# Caprica_Charger.net
KiCad netlist of a schematic drawn in EAGLE
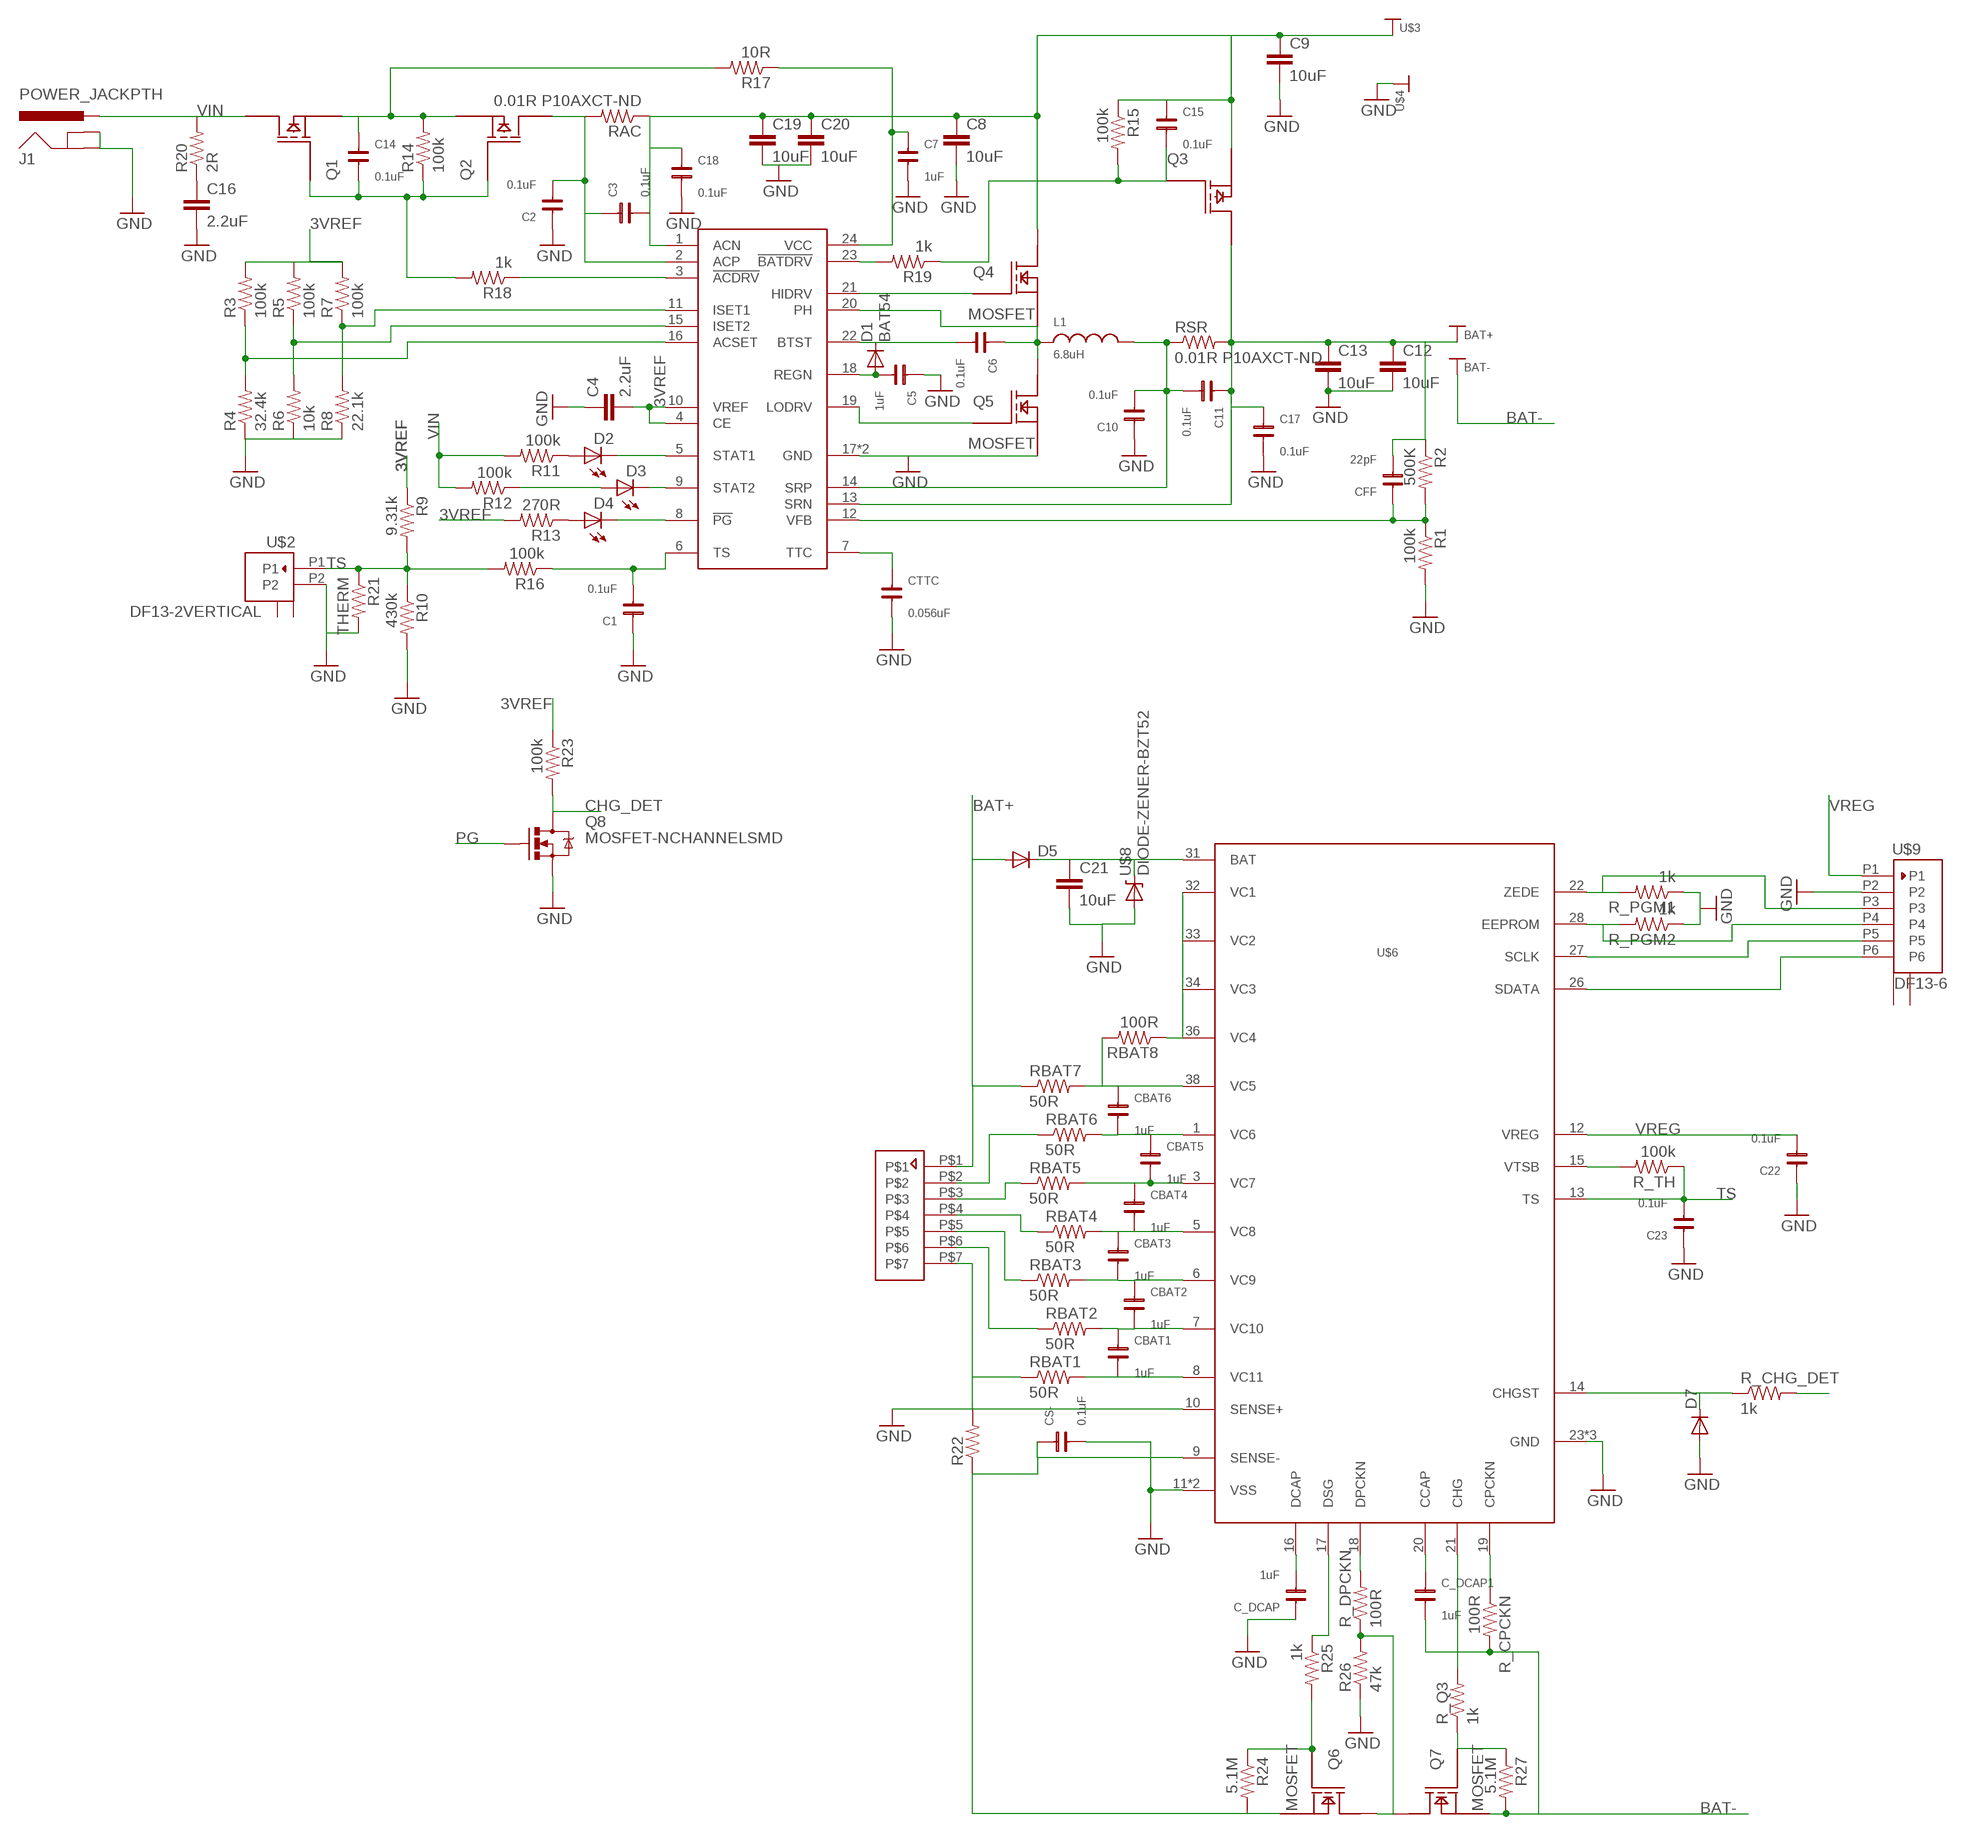
[diagram p0: schematic, sheet 1]

(export (version "E")
  (design (tool "Eeschema 10.0.6"))
  (components
    (comp (ref "BAT+")
      (value "HIGHCURRENTPAD2")
      (footprint "eagle-import:HIGH_CURRENT_PAD2")
      (libsource (lib "eagle-import") (part "HIGHCURRENTPAD2"))
    )
    (comp (ref "BAT-")
      (value "HIGHCURRENTPAD2")
      (footprint "eagle-import:HIGH_CURRENT_PAD2")
      (libsource (lib "eagle-import") (part "HIGHCURRENTPAD2"))
    )
    (comp (ref "C1")
      (value "0.1uF")
      (footprint "eagle-import:0603-CAP")
      (libsource (lib "eagle-import") (part "CAPACITOR0603-CAP"))
    )
    (comp (ref "C2")
      (value "0.1uF")
      (footprint "eagle-import:0603-CAP")
      (libsource (lib "eagle-import") (part "CAPACITOR0603-CAP"))
    )
    (comp (ref "C3")
      (value "0.1uF")
      (footprint "eagle-import:0603-CAP")
      (libsource (lib "eagle-import") (part "CAPACITOR0603-CAP"))
    )
    (comp (ref "C4")
      (value "2.2uF")
      (footprint "eagle-import:1206")
      (libsource (lib "eagle-import") (part "CAP1206"))
    )
    (comp (ref "C5")
      (value "1uF")
      (footprint "eagle-import:0603-CAP")
      (libsource (lib "eagle-import") (part "CAPACITOR0603-CAP"))
    )
    (comp (ref "C6")
      (value "0.1uF")
      (footprint "eagle-import:0603-CAP")
      (libsource (lib "eagle-import") (part "CAPACITOR0603-CAP"))
    )
    (comp (ref "C7")
      (value "1uF")
      (footprint "eagle-import:0603-CAP")
      (libsource (lib "eagle-import") (part "CAPACITOR0603-CAP"))
    )
    (comp (ref "C8")
      (value "10uF")
      (footprint "eagle-import:1206")
      (libsource (lib "eagle-import") (part "CAP1206"))
    )
    (comp (ref "C9")
      (value "10uF")
      (footprint "eagle-import:1206")
      (libsource (lib "eagle-import") (part "CAP1206"))
    )
    (comp (ref "C10")
      (value "0.1uF")
      (footprint "eagle-import:0603-CAP")
      (libsource (lib "eagle-import") (part "CAPACITOR0603-CAP"))
    )
    (comp (ref "C11")
      (value "0.1uF")
      (footprint "eagle-import:0603-CAP")
      (libsource (lib "eagle-import") (part "CAPACITOR0603-CAP"))
    )
    (comp (ref "C12")
      (value "10uF")
      (footprint "eagle-import:1206")
      (libsource (lib "eagle-import") (part "CAP1206"))
    )
    (comp (ref "C13")
      (value "10uF")
      (footprint "eagle-import:1206")
      (libsource (lib "eagle-import") (part "CAP1206"))
    )
    (comp (ref "C14")
      (value "0.1uF")
      (footprint "eagle-import:0603-CAP")
      (libsource (lib "eagle-import") (part "CAPACITOR0603-CAP"))
    )
    (comp (ref "C15")
      (value "0.1uF")
      (footprint "eagle-import:0603-CAP")
      (libsource (lib "eagle-import") (part "CAPACITOR0603-CAP"))
    )
    (comp (ref "C16")
      (value "2.2uF")
      (footprint "eagle-import:1206")
      (libsource (lib "eagle-import") (part "CAP1206"))
    )
    (comp (ref "C17")
      (value "0.1uF")
      (footprint "eagle-import:0603-CAP")
      (libsource (lib "eagle-import") (part "CAPACITOR0603-CAP"))
    )
    (comp (ref "C18")
      (value "0.1uF")
      (footprint "eagle-import:0603-CAP")
      (libsource (lib "eagle-import") (part "CAPACITOR0603-CAP"))
    )
    (comp (ref "C19")
      (value "10uF")
      (footprint "eagle-import:1206")
      (libsource (lib "eagle-import") (part "CAP1206"))
    )
    (comp (ref "C20")
      (value "10uF")
      (footprint "eagle-import:1206")
      (libsource (lib "eagle-import") (part "CAP1206"))
    )
    (comp (ref "C21")
      (value "10uF")
      (footprint "eagle-import:1206")
      (libsource (lib "eagle-import") (part "CAP1206"))
    )
    (comp (ref "C22")
      (value "0.1uF")
      (footprint "eagle-import:0603-CAP")
      (libsource (lib "eagle-import") (part "CAPACITOR0603-CAP"))
    )
    (comp (ref "C23")
      (value "0.1uF")
      (footprint "eagle-import:0603-CAP")
      (libsource (lib "eagle-import") (part "CAPACITOR0603-CAP"))
    )
    (comp (ref "CBAT1")
      (value "1uF")
      (footprint "eagle-import:0603-CAP")
      (libsource (lib "eagle-import") (part "CAPACITOR0603-CAP"))
    )
    (comp (ref "CBAT2")
      (value "1uF")
      (footprint "eagle-import:0603-CAP")
      (libsource (lib "eagle-import") (part "CAPACITOR0603-CAP"))
    )
    (comp (ref "CBAT3")
      (value "1uF")
      (footprint "eagle-import:0603-CAP")
      (libsource (lib "eagle-import") (part "CAPACITOR0603-CAP"))
    )
    (comp (ref "CBAT4")
      (value "1uF")
      (footprint "eagle-import:0603-CAP")
      (libsource (lib "eagle-import") (part "CAPACITOR0603-CAP"))
    )
    (comp (ref "CBAT5")
      (value "1uF")
      (footprint "eagle-import:0603-CAP")
      (libsource (lib "eagle-import") (part "CAPACITOR0603-CAP"))
    )
    (comp (ref "CBAT6")
      (value "1uF")
      (footprint "eagle-import:0603-CAP")
      (libsource (lib "eagle-import") (part "CAPACITOR0603-CAP"))
    )
    (comp (ref "CFF")
      (value "22pF")
      (footprint "eagle-import:0603-CAP")
      (libsource (lib "eagle-import") (part "CAPACITOR0603-CAP"))
    )
    (comp (ref "CS-")
      (value "0.1uF")
      (footprint "eagle-import:0603-CAP")
      (libsource (lib "eagle-import") (part "CAPACITOR0603-CAP"))
    )
    (comp (ref "CTTC")
      (value "0.056uF")
      (footprint "eagle-import:0603-CAP")
      (libsource (lib "eagle-import") (part "CAPACITOR0603-CAP"))
    )
    (comp (ref "C_DCAP")
      (value "1uF")
      (footprint "eagle-import:0603-CAP")
      (libsource (lib "eagle-import") (part "CAPACITOR0603-CAP"))
    )
    (comp (ref "C_DCAP1")
      (value "1uF")
      (footprint "eagle-import:0603-CAP")
      (libsource (lib "eagle-import") (part "CAPACITOR0603-CAP"))
    )
    (comp (ref "D1")
      (value "BAT54")
      (footprint "eagle-import:SOT23-3")
      (libsource (lib "eagle-import") (part "DIODESOT23"))
    )
    (comp (ref "D2")
      (value "LED1206")
      (footprint "eagle-import:LED-1206")
      (libsource (lib "eagle-import") (part "LED1206"))
    )
    (comp (ref "D3")
      (value "LED1206")
      (footprint "eagle-import:LED-1206")
      (libsource (lib "eagle-import") (part "LED1206"))
    )
    (comp (ref "D4")
      (value "LED1206")
      (footprint "eagle-import:LED-1206")
      (libsource (lib "eagle-import") (part "LED1206"))
    )
    (comp (ref "D5")
      (value "DIODESMA")
      (footprint "eagle-import:SMA-DIODE")
      (libsource (lib "eagle-import") (part "DIODESMA"))
    )
    (comp (ref "D7")
      (value "DIODESOD")
      (footprint "eagle-import:SOD-323")
      (libsource (lib "eagle-import") (part "DIODESOD"))
    )
    (comp (ref "J1")
      (value "POWER_JACKPTH")
      (footprint "eagle-import:POWER_JACK_PTH")
      (libsource (lib "eagle-import") (part "POWER_JACKPTH"))
    )
    (comp (ref "L1")
      (value "6.8uH")
      (footprint "eagle-import:SDR0403_INDUCTOR")
      (libsource (lib "eagle-import") (part "INDUCTORSDR0403"))
    )
    (comp (ref "Q1")
      (value "MOSFET_PCH")
      (footprint "eagle-import:POWERPAK_1212-8")
      (libsource (lib "eagle-import") (part "MOSFET_PCH"))
    )
    (comp (ref "Q2")
      (value "MOSFET_PCH")
      (footprint "eagle-import:POWERPAK_1212-8")
      (libsource (lib "eagle-import") (part "MOSFET_PCH"))
    )
    (comp (ref "Q3")
      (value "MOSFET_PCH")
      (footprint "eagle-import:POWERPAK_1212-8")
      (libsource (lib "eagle-import") (part "MOSFET_PCH"))
    )
    (comp (ref "Q4")
      (value "MOSFET")
      (footprint "eagle-import:POWERPAK_1212-8")
      (libsource (lib "eagle-import") (part "MOSFET"))
    )
    (comp (ref "Q5")
      (value "MOSFET")
      (footprint "eagle-import:POWERPAK_1212-8")
      (libsource (lib "eagle-import") (part "MOSFET"))
    )
    (comp (ref "Q6")
      (value "MOSFET")
      (footprint "eagle-import:POWERPAK_1212-8")
      (libsource (lib "eagle-import") (part "MOSFET"))
    )
    (comp (ref "Q7")
      (value "MOSFET")
      (footprint "eagle-import:POWERPAK_1212-8")
      (libsource (lib "eagle-import") (part "MOSFET"))
    )
    (comp (ref "Q8")
      (value "MOSFET-NCHANNELSMD")
      (footprint "eagle-import:SOT23-3")
      (libsource (lib "eagle-import") (part "MOSFET-NCHANNELSMD"))
    )
    (comp (ref "R1")
      (value "100k")
      (footprint "eagle-import:0603-RES")
      (libsource (lib "eagle-import") (part "RESISTOR"))
    )
    (comp (ref "R2")
      (value "500K")
      (footprint "eagle-import:0603-RES")
      (libsource (lib "eagle-import") (part "RESISTOR"))
    )
    (comp (ref "R3")
      (value "100k")
      (footprint "eagle-import:0603-RES")
      (libsource (lib "eagle-import") (part "RESISTOR"))
    )
    (comp (ref "R4")
      (value "32.4k")
      (footprint "eagle-import:0603-RES")
      (libsource (lib "eagle-import") (part "RESISTOR"))
    )
    (comp (ref "R5")
      (value "100k")
      (footprint "eagle-import:0603-RES")
      (libsource (lib "eagle-import") (part "RESISTOR"))
    )
    (comp (ref "R6")
      (value "10k")
      (footprint "eagle-import:0603-RES")
      (libsource (lib "eagle-import") (part "RESISTOR"))
    )
    (comp (ref "R7")
      (value "100k")
      (footprint "eagle-import:0603-RES")
      (libsource (lib "eagle-import") (part "RESISTOR"))
    )
    (comp (ref "R8")
      (value "22.1k")
      (footprint "eagle-import:0603-RES")
      (libsource (lib "eagle-import") (part "RESISTOR"))
    )
    (comp (ref "R9")
      (value "9.31k")
      (footprint "eagle-import:0603-RES")
      (libsource (lib "eagle-import") (part "RESISTOR"))
    )
    (comp (ref "R10")
      (value "430k")
      (footprint "eagle-import:0603-RES")
      (libsource (lib "eagle-import") (part "RESISTOR"))
    )
    (comp (ref "R11")
      (value "100k")
      (footprint "eagle-import:0603-RES")
      (libsource (lib "eagle-import") (part "RESISTOR"))
    )
    (comp (ref "R12")
      (value "100k")
      (footprint "eagle-import:0603-RES")
      (libsource (lib "eagle-import") (part "RESISTOR"))
    )
    (comp (ref "R13")
      (value "270R")
      (footprint "eagle-import:0603-RES")
      (libsource (lib "eagle-import") (part "RESISTOR"))
    )
    (comp (ref "R14")
      (value "100k")
      (footprint "eagle-import:0603-RES")
      (libsource (lib "eagle-import") (part "RESISTOR"))
    )
    (comp (ref "R15")
      (value "100k")
      (footprint "eagle-import:0603-RES")
      (libsource (lib "eagle-import") (part "RESISTOR"))
    )
    (comp (ref "R16")
      (value "100k")
      (footprint "eagle-import:0603-RES")
      (libsource (lib "eagle-import") (part "RESISTOR"))
    )
    (comp (ref "R17")
      (value "10R")
      (footprint "eagle-import:0603-RES")
      (libsource (lib "eagle-import") (part "RESISTOR"))
    )
    (comp (ref "R18")
      (value "1k")
      (footprint "eagle-import:0603-RES")
      (libsource (lib "eagle-import") (part "RESISTOR"))
    )
    (comp (ref "R19")
      (value "1k")
      (footprint "eagle-import:0603-RES")
      (libsource (lib "eagle-import") (part "RESISTOR"))
    )
    (comp (ref "R20")
      (value "2R")
      (footprint "eagle-import:0603-RES")
      (libsource (lib "eagle-import") (part "RESISTOR"))
    )
    (comp (ref "R21")
      (value "THERM")
      (footprint "eagle-import:0603-RES")
      (libsource (lib "eagle-import") (part "RESISTOR"))
    )
    (comp (ref "R22")
      (value "RESISTOROHMITE")
      (footprint "eagle-import:OHMITE_FCSL64_CURRENT_SENSE_RESISTOR")
      (libsource (lib "eagle-import") (part "RESISTOROHMITE"))
    )
    (comp (ref "R23")
      (value "100k")
      (footprint "eagle-import:0603-RES")
      (libsource (lib "eagle-import") (part "RESISTOR"))
    )
    (comp (ref "R24")
      (value "5.1M")
      (footprint "eagle-import:0603-RES")
      (libsource (lib "eagle-import") (part "RESISTOR"))
    )
    (comp (ref "R25")
      (value "1k")
      (footprint "eagle-import:0603-RES")
      (libsource (lib "eagle-import") (part "RESISTOR"))
    )
    (comp (ref "R26")
      (value "47k")
      (footprint "eagle-import:0603-RES")
      (libsource (lib "eagle-import") (part "RESISTOR"))
    )
    (comp (ref "R27")
      (value "5.1M")
      (footprint "eagle-import:0603-RES")
      (libsource (lib "eagle-import") (part "RESISTOR"))
    )
    (comp (ref "RAC")
      (value "0.01R P10AXCT-ND")
      (footprint "eagle-import:0603-RES")
      (libsource (lib "eagle-import") (part "RESISTOR"))
    )
    (comp (ref "RBAT1")
      (value "50R")
      (footprint "eagle-import:0603-RES")
      (libsource (lib "eagle-import") (part "RESISTOR"))
    )
    (comp (ref "RBAT2")
      (value "50R")
      (footprint "eagle-import:0603-RES")
      (libsource (lib "eagle-import") (part "RESISTOR"))
    )
    (comp (ref "RBAT3")
      (value "50R")
      (footprint "eagle-import:0603-RES")
      (libsource (lib "eagle-import") (part "RESISTOR"))
    )
    (comp (ref "RBAT4")
      (value "50R")
      (footprint "eagle-import:0603-RES")
      (libsource (lib "eagle-import") (part "RESISTOR"))
    )
    (comp (ref "RBAT5")
      (value "50R")
      (footprint "eagle-import:0603-RES")
      (libsource (lib "eagle-import") (part "RESISTOR"))
    )
    (comp (ref "RBAT6")
      (value "50R")
      (footprint "eagle-import:0603-RES")
      (libsource (lib "eagle-import") (part "RESISTOR"))
    )
    (comp (ref "RBAT7")
      (value "50R")
      (footprint "eagle-import:0603-RES")
      (libsource (lib "eagle-import") (part "RESISTOR"))
    )
    (comp (ref "RBAT8")
      (value "100R")
      (footprint "eagle-import:0603-RES")
      (libsource (lib "eagle-import") (part "RESISTOR"))
    )
    (comp (ref "RSR")
      (value "0.01R P10AXCT-ND")
      (footprint "eagle-import:0603-RES")
      (libsource (lib "eagle-import") (part "RESISTOR"))
    )
    (comp (ref "R_CHG_DET")
      (value "1k")
      (footprint "eagle-import:0603-RES")
      (libsource (lib "eagle-import") (part "RESISTOR"))
    )
    (comp (ref "R_CPCKN")
      (value "100R")
      (footprint "eagle-import:0603-RES")
      (libsource (lib "eagle-import") (part "RESISTOR"))
    )
    (comp (ref "R_DPCKN")
      (value "100R")
      (footprint "eagle-import:0603-RES")
      (libsource (lib "eagle-import") (part "RESISTOR"))
    )
    (comp (ref "R_PGM1")
      (value "1k")
      (footprint "eagle-import:0603-RES")
      (libsource (lib "eagle-import") (part "RESISTOR"))
    )
    (comp (ref "R_PGM2")
      (value "1k")
      (footprint "eagle-import:0603-RES")
      (libsource (lib "eagle-import") (part "RESISTOR"))
    )
    (comp (ref "R_Q3")
      (value "1k")
      (footprint "eagle-import:0603-RES")
      (libsource (lib "eagle-import") (part "RESISTOR"))
    )
    (comp (ref "R_TH")
      (value "100k")
      (footprint "eagle-import:0603-RES")
      (libsource (lib "eagle-import") (part "RESISTOR"))
    )
    (comp (ref "U$1")
      (value "BQ24610_LIPO_CHARGER")
      (footprint "eagle-import:QFN-24_ALT2")
      (libsource (lib "eagle-import") (part "BQ24610_LIPO_CHARGER"))
    )
    (comp (ref "U$2")
      (value "DF13-2VERTICAL")
      (footprint "eagle-import:DF13-2-VERT")
      (libsource (lib "eagle-import") (part "DF13-2VERTICAL"))
    )
    (comp (ref "U$3")
      (value "HIGHCURRENTPAD2")
      (footprint "eagle-import:HIGH_CURRENT_PAD2")
      (libsource (lib "eagle-import") (part "HIGHCURRENTPAD2"))
    )
    (comp (ref "U$4")
      (value "HIGHCURRENTPAD2")
      (footprint "eagle-import:HIGH_CURRENT_PAD2")
      (libsource (lib "eagle-import") (part "HIGHCURRENTPAD2"))
    )
    (comp (ref "U$6")
      (value "BQ77910A_BATTERY_PROTECTOR")
      (footprint "eagle-import:TSSOP38")
      (libsource (lib "eagle-import") (part "BQ77910A_BATTERY_PROTECTOR"))
    )
    (comp (ref "U$7")
      (value "JST_XH_7")
      (footprint "eagle-import:B7B-XH")
      (libsource (lib "eagle-import") (part "JST_XH_7"))
    )
    (comp (ref "U$8")
      (value "DIODE-ZENER-BZT52")
      (footprint "eagle-import:SOD-323")
      (libsource (lib "eagle-import") (part "DIODE-ZENER-BZT52"))
    )
    (comp (ref "U$9")
      (value "DF13-6")
      (footprint "eagle-import:DF13-6-VERT")
      (libsource (lib "eagle-import") (part "DF13-6"))
    )
  )
  (nets
    (net (code "1") (name "/3VREF") (class "Default")
      (node (ref "C4") (pin "2") (pinfunction "2_2") (pintype "passive"))
      (node (ref "R13") (pin "2") (pinfunction "2_2") (pintype "passive"))
      (node (ref "R23") (pin "1") (pinfunction "1_1") (pintype "passive"))
      (node (ref "R3") (pin "2") (pinfunction "2_2") (pintype "passive"))
      (node (ref "R5") (pin "2") (pinfunction "2_2") (pintype "passive"))
      (node (ref "R7") (pin "2") (pinfunction "2_2") (pintype "passive"))
      (node (ref "R9") (pin "1") (pinfunction "1_1") (pintype "passive"))
      (node (ref "U$1") (pin "10") (pinfunction "VREF_10") (pintype "bidirectional"))
      (node (ref "U$1") (pin "4") (pinfunction "CE_4") (pintype "bidirectional"))
    )
    (net (code "2") (name "/BAT+") (class "Default")
      (node (ref "BAT+") (pin "P$1") (pinfunction "P$1_P$1") (pintype "bidirectional"))
      (node (ref "C11") (pin "1") (pinfunction "1_1") (pintype "bidirectional"))
      (node (ref "C12") (pin "1") (pinfunction "1_1") (pintype "passive"))
      (node (ref "C13") (pin "1") (pinfunction "1_1") (pintype "passive"))
      (node (ref "C17") (pin "1") (pinfunction "1_1") (pintype "bidirectional"))
      (node (ref "CFF") (pin "2") (pinfunction "2_2") (pintype "bidirectional"))
      (node (ref "D5") (pin "A") (pinfunction "A_A") (pintype "passive"))
      (node (ref "Q3") (pin "P5") (pinfunction "DRAIN_P5") (pintype "power_in"))
      (node (ref "Q3") (pin "P6") (pinfunction "DRAIN_P6") (pintype "power_in"))
      (node (ref "Q3") (pin "P7") (pinfunction "DRAIN_P7") (pintype "power_in"))
      (node (ref "Q3") (pin "P8") (pinfunction "DRAIN_P8") (pintype "power_in"))
      (node (ref "Q3") (pin "PAD") (pinfunction "DRAIN_PAD") (pintype "power_in"))
      (node (ref "R2") (pin "1") (pinfunction "1_1") (pintype "passive"))
      (node (ref "RBAT7") (pin "1") (pinfunction "1_1") (pintype "passive"))
      (node (ref "RSR") (pin "2") (pinfunction "2_2") (pintype "passive"))
      (node (ref "U$1") (pin "13") (pinfunction "SRN_13") (pintype "bidirectional"))
      (node (ref "U$7") (pin "P$1") (pinfunction "P$1_P$1") (pintype "bidirectional"))
    )
    (net (code "3") (name "/BAT-") (class "Default")
      (node (ref "BAT-") (pin "P$1") (pinfunction "P$1_P$1") (pintype "bidirectional"))
      (node (ref "C_DCAP1") (pin "2") (pinfunction "2_2") (pintype "bidirectional"))
      (node (ref "Q7") (pin "P1") (pinfunction "S_P1") (pintype "bidirectional"))
      (node (ref "Q7") (pin "P2") (pinfunction "S_P2") (pintype "bidirectional"))
      (node (ref "Q7") (pin "P3") (pinfunction "S_P3") (pintype "bidirectional"))
      (node (ref "R27") (pin "2") (pinfunction "2_2") (pintype "passive"))
      (node (ref "R_CPCKN") (pin "2") (pinfunction "2_2") (pintype "passive"))
    )
    (net (code "4") (name "/CHG_DET") (class "Default")
      (node (ref "Q8") (pin "3") (pinfunction "D_3") (pintype "passive"))
      (node (ref "R23") (pin "2") (pinfunction "2_2") (pintype "passive"))
      (node (ref "R_CHG_DET") (pin "2") (pinfunction "2_2") (pintype "passive"))
    )
    (net (code "5") (name "/PG") (class "Default")
      (node (ref "D4") (pin "C") (pinfunction "C_C") (pintype "passive"))
      (node (ref "Q8") (pin "1") (pinfunction "G_1") (pintype "passive"))
      (node (ref "U$1") (pin "8") (pinfunction "~{PG}_8") (pintype "bidirectional"))
    )
    (net (code "6") (name "/TS") (class "Default")
      (node (ref "C23") (pin "2") (pinfunction "2_2") (pintype "bidirectional"))
      (node (ref "R10") (pin "1") (pinfunction "1_1") (pintype "passive"))
      (node (ref "R16") (pin "2") (pinfunction "2_2") (pintype "passive"))
      (node (ref "R21") (pin "1") (pinfunction "1_1") (pintype "passive"))
      (node (ref "R9") (pin "2") (pinfunction "2_2") (pintype "passive"))
      (node (ref "R_TH") (pin "1") (pinfunction "1_1") (pintype "passive"))
      (node (ref "U$2") (pin "P1") (pinfunction "P1_P1") (pintype "bidirectional"))
      (node (ref "U$6") (pin "13") (pinfunction "TS_13") (pintype "bidirectional"))
    )
    (net (code "7") (name "/VIN") (class "Default")
      (node (ref "J1") (pin "PWR") (pinfunction "PWR_PWR") (pintype "bidirectional"))
      (node (ref "Q1") (pin "P5") (pinfunction "DRAIN_P5") (pintype "power_in"))
      (node (ref "Q1") (pin "P6") (pinfunction "DRAIN_P6") (pintype "power_in"))
      (node (ref "Q1") (pin "P7") (pinfunction "DRAIN_P7") (pintype "power_in"))
      (node (ref "Q1") (pin "P8") (pinfunction "DRAIN_P8") (pintype "power_in"))
      (node (ref "Q1") (pin "PAD") (pinfunction "DRAIN_PAD") (pintype "power_in"))
      (node (ref "R11") (pin "2") (pinfunction "2_2") (pintype "passive"))
      (node (ref "R12") (pin "2") (pinfunction "2_2") (pintype "passive"))
      (node (ref "R20") (pin "2") (pinfunction "2_2") (pintype "passive"))
    )
    (net (code "8") (name "/VREG") (class "Default")
      (node (ref "C22") (pin "2") (pinfunction "2_2") (pintype "bidirectional"))
      (node (ref "U$6") (pin "12") (pinfunction "VREG_12") (pintype "bidirectional"))
      (node (ref "U$9") (pin "P1") (pinfunction "P1_P1") (pintype "bidirectional"))
    )
    (net (code "9") (name "GND") (class "Default")
      (node (ref "C1") (pin "1") (pinfunction "1_1") (pintype "bidirectional"))
      (node (ref "C10") (pin "1") (pinfunction "1_1") (pintype "bidirectional"))
      (node (ref "C12") (pin "2") (pinfunction "2_2") (pintype "passive"))
      (node (ref "C13") (pin "2") (pinfunction "2_2") (pintype "passive"))
      (node (ref "C16") (pin "2") (pinfunction "2_2") (pintype "passive"))
      (node (ref "C17") (pin "2") (pinfunction "2_2") (pintype "bidirectional"))
      (node (ref "C18") (pin "2") (pinfunction "2_2") (pintype "bidirectional"))
      (node (ref "C19") (pin "2") (pinfunction "2_2") (pintype "passive"))
      (node (ref "C2") (pin "1") (pinfunction "1_1") (pintype "bidirectional"))
      (node (ref "C20") (pin "2") (pinfunction "2_2") (pintype "passive"))
      (node (ref "C21") (pin "2") (pinfunction "2_2") (pintype "passive"))
      (node (ref "C22") (pin "1") (pinfunction "1_1") (pintype "bidirectional"))
      (node (ref "C23") (pin "1") (pinfunction "1_1") (pintype "bidirectional"))
      (node (ref "C4") (pin "1") (pinfunction "1_1") (pintype "passive"))
      (node (ref "C5") (pin "1") (pinfunction "1_1") (pintype "bidirectional"))
      (node (ref "C7") (pin "2") (pinfunction "2_2") (pintype "bidirectional"))
      (node (ref "C8") (pin "2") (pinfunction "2_2") (pintype "passive"))
      (node (ref "C9") (pin "2") (pinfunction "2_2") (pintype "passive"))
      (node (ref "CS-") (pin "2") (pinfunction "2_2") (pintype "bidirectional"))
      (node (ref "CTTC") (pin "2") (pinfunction "2_2") (pintype "bidirectional"))
      (node (ref "C_DCAP") (pin "1") (pinfunction "1_1") (pintype "bidirectional"))
      (node (ref "D7") (pin "2") (pinfunction "A_2") (pintype "passive"))
      (node (ref "J1") (pin "GND") (pinfunction "GND_GND") (pintype "bidirectional"))
      (node (ref "J1") (pin "GNDBREAK") (pinfunction "GNDBREAK_GNDBREAK") (pintype "bidirectional"))
      (node (ref "Q5") (pin "P1") (pinfunction "S_P1") (pintype "bidirectional"))
      (node (ref "Q5") (pin "P2") (pinfunction "S_P2") (pintype "bidirectional"))
      (node (ref "Q5") (pin "P3") (pinfunction "S_P3") (pintype "bidirectional"))
      (node (ref "Q8") (pin "2") (pinfunction "S_2") (pintype "passive"))
      (node (ref "R1") (pin "2") (pinfunction "2_2") (pintype "passive"))
      (node (ref "R10") (pin "2") (pinfunction "2_2") (pintype "passive"))
      (node (ref "R21") (pin "2") (pinfunction "2_2") (pintype "passive"))
      (node (ref "R22") (pin "P$2") (pinfunction "2_P$2") (pintype "passive"))
      (node (ref "R26") (pin "1") (pinfunction "1_1") (pintype "passive"))
      (node (ref "R4") (pin "1") (pinfunction "1_1") (pintype "passive"))
      (node (ref "R6") (pin "1") (pinfunction "1_1") (pintype "passive"))
      (node (ref "R8") (pin "1") (pinfunction "1_1") (pintype "passive"))
      (node (ref "RBAT1") (pin "1") (pinfunction "1_1") (pintype "passive"))
      (node (ref "R_PGM1") (pin "1") (pinfunction "1_1") (pintype "passive"))
      (node (ref "R_PGM2") (pin "1") (pinfunction "1_1") (pintype "passive"))
      (node (ref "U$1") (pin "17") (pinfunction "GND_17") (pintype "bidirectional"))
      (node (ref "U$1") (pin "EP") (pinfunction "GND_EP") (pintype "bidirectional"))
      (node (ref "U$2") (pin "P2") (pinfunction "P2_P2") (pintype "bidirectional"))
      (node (ref "U$4") (pin "P$1") (pinfunction "P$1_P$1") (pintype "bidirectional"))
      (node (ref "U$6") (pin "10") (pinfunction "SENSE+_10") (pintype "bidirectional"))
      (node (ref "U$6") (pin "11") (pinfunction "VSS_11") (pintype "bidirectional"))
      (node (ref "U$6") (pin "23") (pinfunction "GND_23") (pintype "bidirectional"))
      (node (ref "U$6") (pin "24") (pinfunction "GND_24") (pintype "bidirectional"))
      (node (ref "U$6") (pin "25") (pinfunction "GND_25") (pintype "bidirectional"))
      (node (ref "U$6") (pin "29") (pinfunction "VSS_29") (pintype "bidirectional"))
      (node (ref "U$7") (pin "P$7") (pinfunction "P$7_P$7") (pintype "bidirectional"))
      (node (ref "U$8") (pin "2") (pinfunction "A_2") (pintype "passive"))
      (node (ref "U$9") (pin "P2") (pinfunction "P2_P2") (pintype "bidirectional"))
    )
    (net (code "10") (name "Net-(C14-Pad1)") (class "Default")
      (node (ref "C14") (pin "1") (pinfunction "1_1") (pintype "bidirectional"))
      (node (ref "Q1") (pin "P1") (pinfunction "SOURCE_P1") (pintype "bidirectional"))
      (node (ref "Q1") (pin "P2") (pinfunction "SOURCE_P2") (pintype "bidirectional"))
      (node (ref "Q1") (pin "P3") (pinfunction "SOURCE_P3") (pintype "bidirectional"))
      (node (ref "Q2") (pin "P1") (pinfunction "SOURCE_P1") (pintype "bidirectional"))
      (node (ref "Q2") (pin "P2") (pinfunction "SOURCE_P2") (pintype "bidirectional"))
      (node (ref "Q2") (pin "P3") (pinfunction "SOURCE_P3") (pintype "bidirectional"))
      (node (ref "R14") (pin "2") (pinfunction "2_2") (pintype "passive"))
      (node (ref "R17") (pin "2") (pinfunction "2_2") (pintype "passive"))
    )
    (net (code "11") (name "Net-(C16-Pad1)") (class "Default")
      (node (ref "C16") (pin "1") (pinfunction "1_1") (pintype "passive"))
      (node (ref "R20") (pin "1") (pinfunction "1_1") (pintype "passive"))
    )
    (net (code "12") (name "Net-(D1-A)") (class "Default")
      (node (ref "C5") (pin "2") (pinfunction "2_2") (pintype "bidirectional"))
      (node (ref "D1") (pin "1") (pinfunction "A_1") (pintype "passive"))
      (node (ref "U$1") (pin "18") (pinfunction "REGN_18") (pintype "bidirectional"))
    )
    (net (code "13") (name "Net-(D1-C)") (class "Default")
      (node (ref "C6") (pin "2") (pinfunction "2_2") (pintype "bidirectional"))
      (node (ref "D1") (pin "3") (pinfunction "C_3") (pintype "passive"))
      (node (ref "U$1") (pin "22") (pinfunction "BTST_22") (pintype "bidirectional"))
    )
    (net (code "14") (name "Net-(D2-PadA)") (class "Default")
      (node (ref "D2") (pin "A") (pinfunction "A_A") (pintype "passive"))
      (node (ref "R11") (pin "1") (pinfunction "1_1") (pintype "passive"))
    )
    (net (code "15") (name "Net-(D3-PadA)") (class "Default")
      (node (ref "D3") (pin "A") (pinfunction "A_A") (pintype "passive"))
      (node (ref "R12") (pin "1") (pinfunction "1_1") (pintype "passive"))
    )
    (net (code "16") (name "Net-(D4-PadA)") (class "Default")
      (node (ref "D4") (pin "A") (pinfunction "A_A") (pintype "passive"))
      (node (ref "R13") (pin "1") (pinfunction "1_1") (pintype "passive"))
    )
    (net (code "17") (name "Net-(D7-C)") (class "Default")
      (node (ref "D7") (pin "1") (pinfunction "C_1") (pintype "passive"))
      (node (ref "R_CHG_DET") (pin "1") (pinfunction "1_1") (pintype "passive"))
      (node (ref "U$6") (pin "14") (pinfunction "CHGST_14") (pintype "bidirectional"))
    )
    (net (code "18") (name "Net-(Q1-GATE)") (class "Default")
      (node (ref "C14") (pin "2") (pinfunction "2_2") (pintype "bidirectional"))
      (node (ref "Q1") (pin "P4") (pinfunction "GATE_P4") (pintype "bidirectional"))
      (node (ref "Q2") (pin "P4") (pinfunction "GATE_P4") (pintype "bidirectional"))
      (node (ref "R14") (pin "1") (pinfunction "1_1") (pintype "passive"))
      (node (ref "R18") (pin "2") (pinfunction "2_2") (pintype "passive"))
    )
    (net (code "19") (name "Net-(Q3-GATE)") (class "Default")
      (node (ref "C15") (pin "2") (pinfunction "2_2") (pintype "bidirectional"))
      (node (ref "Q3") (pin "P4") (pinfunction "GATE_P4") (pintype "bidirectional"))
      (node (ref "R15") (pin "2") (pinfunction "2_2") (pintype "passive"))
      (node (ref "R19") (pin "1") (pinfunction "1_1") (pintype "passive"))
    )
    (net (code "20") (name "Net-(Q4-G)") (class "Default")
      (node (ref "Q4") (pin "P4") (pinfunction "G_P4") (pintype "bidirectional"))
      (node (ref "U$1") (pin "21") (pinfunction "HIDRV_21") (pintype "bidirectional"))
    )
    (net (code "21") (name "Net-(Q5-G)") (class "Default")
      (node (ref "Q5") (pin "P4") (pinfunction "G_P4") (pintype "bidirectional"))
      (node (ref "U$1") (pin "19") (pinfunction "LODRV_19") (pintype "bidirectional"))
    )
    (net (code "22") (name "Net-(Q6-D-PadP5)") (class "Default")
      (node (ref "Q6") (pin "P5") (pinfunction "D_P5") (pintype "bidirectional"))
      (node (ref "Q6") (pin "P6") (pinfunction "D_P6") (pintype "bidirectional"))
      (node (ref "Q6") (pin "P7") (pinfunction "D_P7") (pintype "bidirectional"))
      (node (ref "Q6") (pin "P8") (pinfunction "D_P8") (pintype "bidirectional"))
      (node (ref "Q6") (pin "PAD") (pinfunction "D_PAD") (pintype "bidirectional"))
      (node (ref "Q7") (pin "P5") (pinfunction "D_P5") (pintype "bidirectional"))
      (node (ref "Q7") (pin "P6") (pinfunction "D_P6") (pintype "bidirectional"))
      (node (ref "Q7") (pin "P7") (pinfunction "D_P7") (pintype "bidirectional"))
      (node (ref "Q7") (pin "P8") (pinfunction "D_P8") (pintype "bidirectional"))
      (node (ref "Q7") (pin "PAD") (pinfunction "D_PAD") (pintype "bidirectional"))
      (node (ref "R26") (pin "2") (pinfunction "2_2") (pintype "passive"))
      (node (ref "R_DPCKN") (pin "1") (pinfunction "1_1") (pintype "passive"))
    )
    (net (code "23") (name "Net-(Q6-G)") (class "Default")
      (node (ref "Q6") (pin "P4") (pinfunction "G_P4") (pintype "bidirectional"))
      (node (ref "R24") (pin "1") (pinfunction "1_1") (pintype "passive"))
      (node (ref "R25") (pin "2") (pinfunction "2_2") (pintype "passive"))
    )
    (net (code "24") (name "Net-(Q7-G)") (class "Default")
      (node (ref "Q7") (pin "P4") (pinfunction "G_P4") (pintype "bidirectional"))
      (node (ref "R27") (pin "1") (pinfunction "1_1") (pintype "passive"))
      (node (ref "R_Q3") (pin "1") (pinfunction "1_1") (pintype "passive"))
    )
    (net (code "25") (name "Net-(R22-1)") (class "Default")
      (node (ref "CS-") (pin "1") (pinfunction "1_1") (pintype "bidirectional"))
      (node (ref "Q6") (pin "P1") (pinfunction "S_P1") (pintype "bidirectional"))
      (node (ref "Q6") (pin "P2") (pinfunction "S_P2") (pintype "bidirectional"))
      (node (ref "Q6") (pin "P3") (pinfunction "S_P3") (pintype "bidirectional"))
      (node (ref "R22") (pin "P$1") (pinfunction "1_P$1") (pintype "passive"))
      (node (ref "R24") (pin "2") (pinfunction "2_2") (pintype "passive"))
      (node (ref "U$6") (pin "9") (pinfunction "SENSE-_9") (pintype "bidirectional"))
    )
    (net (code "26") (name "Net-(RBAT2-Pad1)") (class "Default")
      (node (ref "RBAT2") (pin "1") (pinfunction "1_1") (pintype "passive"))
      (node (ref "U$7") (pin "P$6") (pinfunction "P$6_P$6") (pintype "bidirectional"))
    )
    (net (code "27") (name "Net-(RBAT3-Pad1)") (class "Default")
      (node (ref "RBAT3") (pin "1") (pinfunction "1_1") (pintype "passive"))
      (node (ref "U$7") (pin "P$5") (pinfunction "P$5_P$5") (pintype "bidirectional"))
    )
    (net (code "28") (name "Net-(RBAT4-Pad1)") (class "Default")
      (node (ref "RBAT4") (pin "1") (pinfunction "1_1") (pintype "passive"))
      (node (ref "U$7") (pin "P$4") (pinfunction "P$4_P$4") (pintype "bidirectional"))
    )
    (net (code "29") (name "Net-(RBAT5-Pad1)") (class "Default")
      (node (ref "RBAT5") (pin "1") (pinfunction "1_1") (pintype "passive"))
      (node (ref "U$7") (pin "P$3") (pinfunction "P$3_P$3") (pintype "bidirectional"))
    )
    (net (code "30") (name "Net-(RBAT6-Pad1)") (class "Default")
      (node (ref "RBAT6") (pin "1") (pinfunction "1_1") (pintype "passive"))
      (node (ref "U$7") (pin "P$2") (pinfunction "P$2_P$2") (pintype "bidirectional"))
    )
    (net (code "31") (name "Net-(U$1-ACN)") (class "Default")
      (node (ref "C15") (pin "1") (pinfunction "1_1") (pintype "bidirectional"))
      (node (ref "C18") (pin "1") (pinfunction "1_1") (pintype "bidirectional"))
      (node (ref "C19") (pin "1") (pinfunction "1_1") (pintype "passive"))
      (node (ref "C20") (pin "1") (pinfunction "1_1") (pintype "passive"))
      (node (ref "C3") (pin "2") (pinfunction "2_2") (pintype "bidirectional"))
      (node (ref "C8") (pin "1") (pinfunction "1_1") (pintype "passive"))
      (node (ref "C9") (pin "1") (pinfunction "1_1") (pintype "passive"))
      (node (ref "Q3") (pin "P1") (pinfunction "SOURCE_P1") (pintype "bidirectional"))
      (node (ref "Q3") (pin "P2") (pinfunction "SOURCE_P2") (pintype "bidirectional"))
      (node (ref "Q3") (pin "P3") (pinfunction "SOURCE_P3") (pintype "bidirectional"))
      (node (ref "Q4") (pin "P5") (pinfunction "D_P5") (pintype "bidirectional"))
      (node (ref "Q4") (pin "P6") (pinfunction "D_P6") (pintype "bidirectional"))
      (node (ref "Q4") (pin "P7") (pinfunction "D_P7") (pintype "bidirectional"))
      (node (ref "Q4") (pin "P8") (pinfunction "D_P8") (pintype "bidirectional"))
      (node (ref "Q4") (pin "PAD") (pinfunction "D_PAD") (pintype "bidirectional"))
      (node (ref "R15") (pin "1") (pinfunction "1_1") (pintype "passive"))
      (node (ref "RAC") (pin "1") (pinfunction "1_1") (pintype "passive"))
      (node (ref "U$1") (pin "1") (pinfunction "ACN_1") (pintype "bidirectional"))
      (node (ref "U$3") (pin "P$1") (pinfunction "P$1_P$1") (pintype "bidirectional"))
    )
    (net (code "32") (name "Net-(U$1-ACP)") (class "Default")
      (node (ref "C2") (pin "2") (pinfunction "2_2") (pintype "bidirectional"))
      (node (ref "C3") (pin "1") (pinfunction "1_1") (pintype "bidirectional"))
      (node (ref "Q2") (pin "P5") (pinfunction "DRAIN_P5") (pintype "power_in"))
      (node (ref "Q2") (pin "P6") (pinfunction "DRAIN_P6") (pintype "power_in"))
      (node (ref "Q2") (pin "P7") (pinfunction "DRAIN_P7") (pintype "power_in"))
      (node (ref "Q2") (pin "P8") (pinfunction "DRAIN_P8") (pintype "power_in"))
      (node (ref "Q2") (pin "PAD") (pinfunction "DRAIN_PAD") (pintype "power_in"))
      (node (ref "RAC") (pin "2") (pinfunction "2_2") (pintype "passive"))
      (node (ref "U$1") (pin "2") (pinfunction "ACP_2") (pintype "bidirectional"))
    )
    (net (code "33") (name "Net-(U$1-ACSET)") (class "Default")
      (node (ref "R3") (pin "1") (pinfunction "1_1") (pintype "passive"))
      (node (ref "R4") (pin "2") (pinfunction "2_2") (pintype "passive"))
      (node (ref "U$1") (pin "16") (pinfunction "ACSET_16") (pintype "bidirectional"))
    )
    (net (code "34") (name "Net-(U$1-ISET1)") (class "Default")
      (node (ref "R7") (pin "1") (pinfunction "1_1") (pintype "passive"))
      (node (ref "R8") (pin "2") (pinfunction "2_2") (pintype "passive"))
      (node (ref "U$1") (pin "11") (pinfunction "ISET1_11") (pintype "bidirectional"))
    )
    (net (code "35") (name "Net-(U$1-ISET2)") (class "Default")
      (node (ref "R5") (pin "1") (pinfunction "1_1") (pintype "passive"))
      (node (ref "R6") (pin "2") (pinfunction "2_2") (pintype "passive"))
      (node (ref "U$1") (pin "15") (pinfunction "ISET2_15") (pintype "bidirectional"))
    )
    (net (code "36") (name "Net-(U$1-PH)") (class "Default")
      (node (ref "C6") (pin "1") (pinfunction "1_1") (pintype "bidirectional"))
      (node (ref "L1") (pin "P$1") (pinfunction "P$1_P$1") (pintype "passive"))
      (node (ref "Q4") (pin "P1") (pinfunction "S_P1") (pintype "bidirectional"))
      (node (ref "Q4") (pin "P2") (pinfunction "S_P2") (pintype "bidirectional"))
      (node (ref "Q4") (pin "P3") (pinfunction "S_P3") (pintype "bidirectional"))
      (node (ref "Q5") (pin "P5") (pinfunction "D_P5") (pintype "bidirectional"))
      (node (ref "Q5") (pin "P6") (pinfunction "D_P6") (pintype "bidirectional"))
      (node (ref "Q5") (pin "P7") (pinfunction "D_P7") (pintype "bidirectional"))
      (node (ref "Q5") (pin "P8") (pinfunction "D_P8") (pintype "bidirectional"))
      (node (ref "Q5") (pin "PAD") (pinfunction "D_PAD") (pintype "bidirectional"))
      (node (ref "U$1") (pin "20") (pinfunction "PH_20") (pintype "bidirectional"))
    )
    (net (code "37") (name "Net-(U$1-SRP)") (class "Default")
      (node (ref "C10") (pin "2") (pinfunction "2_2") (pintype "bidirectional"))
      (node (ref "C11") (pin "2") (pinfunction "2_2") (pintype "bidirectional"))
      (node (ref "L1") (pin "P$2") (pinfunction "P$2_P$2") (pintype "passive"))
      (node (ref "RSR") (pin "1") (pinfunction "1_1") (pintype "passive"))
      (node (ref "U$1") (pin "14") (pinfunction "SRP_14") (pintype "bidirectional"))
    )
    (net (code "38") (name "Net-(U$1-STAT1)") (class "Default")
      (node (ref "D2") (pin "C") (pinfunction "C_C") (pintype "passive"))
      (node (ref "U$1") (pin "5") (pinfunction "STAT1_5") (pintype "bidirectional"))
    )
    (net (code "39") (name "Net-(U$1-STAT2)") (class "Default")
      (node (ref "D3") (pin "C") (pinfunction "C_C") (pintype "passive"))
      (node (ref "U$1") (pin "9") (pinfunction "STAT2_9") (pintype "bidirectional"))
    )
    (net (code "40") (name "Net-(U$1-TS)") (class "Default")
      (node (ref "C1") (pin "2") (pinfunction "2_2") (pintype "bidirectional"))
      (node (ref "R16") (pin "1") (pinfunction "1_1") (pintype "passive"))
      (node (ref "U$1") (pin "6") (pinfunction "TS_6") (pintype "bidirectional"))
    )
    (net (code "41") (name "Net-(U$1-TTC)") (class "Default")
      (node (ref "CTTC") (pin "1") (pinfunction "1_1") (pintype "bidirectional"))
      (node (ref "U$1") (pin "7") (pinfunction "TTC_7") (pintype "bidirectional"))
    )
    (net (code "42") (name "Net-(U$1-VCC)") (class "Default")
      (node (ref "C7") (pin "1") (pinfunction "1_1") (pintype "bidirectional"))
      (node (ref "R17") (pin "1") (pinfunction "1_1") (pintype "passive"))
      (node (ref "U$1") (pin "24") (pinfunction "VCC_24") (pintype "bidirectional"))
    )
    (net (code "43") (name "Net-(U$1-VFB)") (class "Default")
      (node (ref "CFF") (pin "1") (pinfunction "1_1") (pintype "bidirectional"))
      (node (ref "R1") (pin "1") (pinfunction "1_1") (pintype "passive"))
      (node (ref "R2") (pin "2") (pinfunction "2_2") (pintype "passive"))
      (node (ref "U$1") (pin "12") (pinfunction "VFB_12") (pintype "bidirectional"))
    )
    (net (code "44") (name "Net-(U$1-~{ACDRV})") (class "Default")
      (node (ref "R18") (pin "1") (pinfunction "1_1") (pintype "passive"))
      (node (ref "U$1") (pin "3") (pinfunction "~{ACDRV}_3") (pintype "bidirectional"))
    )
    (net (code "45") (name "Net-(U$1-~{BATDRV})") (class "Default")
      (node (ref "R19") (pin "2") (pinfunction "2_2") (pintype "passive"))
      (node (ref "U$1") (pin "23") (pinfunction "~{BATDRV}_23") (pintype "bidirectional"))
    )
    (net (code "46") (name "Net-(U$6-BAT)") (class "Default")
      (node (ref "C21") (pin "1") (pinfunction "1_1") (pintype "passive"))
      (node (ref "D5") (pin "C") (pinfunction "C_C") (pintype "passive"))
      (node (ref "U$6") (pin "31") (pinfunction "BAT_31") (pintype "bidirectional"))
      (node (ref "U$8") (pin "1") (pinfunction "C_1") (pintype "passive"))
    )
    (net (code "47") (name "Net-(U$6-CCAP)") (class "Default")
      (node (ref "C_DCAP1") (pin "1") (pinfunction "1_1") (pintype "bidirectional"))
      (node (ref "U$6") (pin "20") (pinfunction "CCAP_20") (pintype "bidirectional"))
    )
    (net (code "48") (name "Net-(U$6-CHG)") (class "Default")
      (node (ref "R_Q3") (pin "2") (pinfunction "2_2") (pintype "passive"))
      (node (ref "U$6") (pin "21") (pinfunction "CHG_21") (pintype "bidirectional"))
    )
    (net (code "49") (name "Net-(U$6-CPCKN)") (class "Default")
      (node (ref "R_CPCKN") (pin "1") (pinfunction "1_1") (pintype "passive"))
      (node (ref "U$6") (pin "19") (pinfunction "CPCKN_19") (pintype "bidirectional"))
    )
    (net (code "50") (name "Net-(U$6-DCAP)") (class "Default")
      (node (ref "C_DCAP") (pin "2") (pinfunction "2_2") (pintype "bidirectional"))
      (node (ref "U$6") (pin "16") (pinfunction "DCAP_16") (pintype "bidirectional"))
    )
    (net (code "51") (name "Net-(U$6-DPCKN)") (class "Default")
      (node (ref "R_DPCKN") (pin "2") (pinfunction "2_2") (pintype "passive"))
      (node (ref "U$6") (pin "18") (pinfunction "DPCKN_18") (pintype "bidirectional"))
    )
    (net (code "52") (name "Net-(U$6-DSG)") (class "Default")
      (node (ref "R25") (pin "1") (pinfunction "1_1") (pintype "passive"))
      (node (ref "U$6") (pin "17") (pinfunction "DSG_17") (pintype "bidirectional"))
    )
    (net (code "53") (name "Net-(U$6-EEPROM)") (class "Default")
      (node (ref "R_PGM2") (pin "2") (pinfunction "2_2") (pintype "passive"))
      (node (ref "U$6") (pin "28") (pinfunction "EEPROM_28") (pintype "bidirectional"))
      (node (ref "U$9") (pin "P4") (pinfunction "P4_P4") (pintype "bidirectional"))
    )
    (net (code "54") (name "Net-(U$6-SCLK)") (class "Default")
      (node (ref "U$6") (pin "27") (pinfunction "SCLK_27") (pintype "bidirectional"))
      (node (ref "U$9") (pin "P5") (pinfunction "P5_P5") (pintype "bidirectional"))
    )
    (net (code "55") (name "Net-(U$6-SDATA)") (class "Default")
      (node (ref "U$6") (pin "26") (pinfunction "SDATA_26") (pintype "bidirectional"))
      (node (ref "U$9") (pin "P6") (pinfunction "P6_P6") (pintype "bidirectional"))
    )
    (net (code "56") (name "Net-(U$6-VC1)") (class "Default")
      (node (ref "RBAT8") (pin "1") (pinfunction "1_1") (pintype "passive"))
      (node (ref "U$6") (pin "32") (pinfunction "VC1_32") (pintype "bidirectional"))
      (node (ref "U$6") (pin "33") (pinfunction "VC2_33") (pintype "bidirectional"))
      (node (ref "U$6") (pin "34") (pinfunction "VC3_34") (pintype "bidirectional"))
      (node (ref "U$6") (pin "36") (pinfunction "VC4_36") (pintype "bidirectional"))
    )
    (net (code "57") (name "Net-(U$6-VC5)") (class "Default")
      (node (ref "CBAT6") (pin "1") (pinfunction "1_1") (pintype "bidirectional"))
      (node (ref "RBAT7") (pin "2") (pinfunction "2_2") (pintype "passive"))
      (node (ref "RBAT8") (pin "2") (pinfunction "2_2") (pintype "passive"))
      (node (ref "U$6") (pin "38") (pinfunction "VC5_38") (pintype "bidirectional"))
    )
    (net (code "58") (name "Net-(U$6-VC6)") (class "Default")
      (node (ref "CBAT5") (pin "1") (pinfunction "1_1") (pintype "bidirectional"))
      (node (ref "CBAT6") (pin "2") (pinfunction "2_2") (pintype "bidirectional"))
      (node (ref "RBAT6") (pin "2") (pinfunction "2_2") (pintype "passive"))
      (node (ref "U$6") (pin "1") (pinfunction "VC6_1") (pintype "bidirectional"))
    )
    (net (code "59") (name "Net-(U$6-VC7)") (class "Default")
      (node (ref "CBAT4") (pin "1") (pinfunction "1_1") (pintype "bidirectional"))
      (node (ref "CBAT5") (pin "2") (pinfunction "2_2") (pintype "bidirectional"))
      (node (ref "RBAT5") (pin "2") (pinfunction "2_2") (pintype "passive"))
      (node (ref "U$6") (pin "3") (pinfunction "VC7_3") (pintype "bidirectional"))
    )
    (net (code "60") (name "Net-(U$6-VC8)") (class "Default")
      (node (ref "CBAT3") (pin "1") (pinfunction "1_1") (pintype "bidirectional"))
      (node (ref "CBAT4") (pin "2") (pinfunction "2_2") (pintype "bidirectional"))
      (node (ref "RBAT4") (pin "2") (pinfunction "2_2") (pintype "passive"))
      (node (ref "U$6") (pin "5") (pinfunction "VC8_5") (pintype "bidirectional"))
    )
    (net (code "61") (name "Net-(U$6-VC9)") (class "Default")
      (node (ref "CBAT2") (pin "1") (pinfunction "1_1") (pintype "bidirectional"))
      (node (ref "CBAT3") (pin "2") (pinfunction "2_2") (pintype "bidirectional"))
      (node (ref "RBAT3") (pin "2") (pinfunction "2_2") (pintype "passive"))
      (node (ref "U$6") (pin "6") (pinfunction "VC9_6") (pintype "bidirectional"))
    )
    (net (code "62") (name "Net-(U$6-VC10)") (class "Default")
      (node (ref "CBAT1") (pin "1") (pinfunction "1_1") (pintype "bidirectional"))
      (node (ref "CBAT2") (pin "2") (pinfunction "2_2") (pintype "bidirectional"))
      (node (ref "RBAT2") (pin "2") (pinfunction "2_2") (pintype "passive"))
      (node (ref "U$6") (pin "7") (pinfunction "VC10_7") (pintype "bidirectional"))
    )
    (net (code "63") (name "Net-(U$6-VC11)") (class "Default")
      (node (ref "CBAT1") (pin "2") (pinfunction "2_2") (pintype "bidirectional"))
      (node (ref "RBAT1") (pin "2") (pinfunction "2_2") (pintype "passive"))
      (node (ref "U$6") (pin "8") (pinfunction "VC11_8") (pintype "bidirectional"))
    )
    (net (code "64") (name "Net-(U$6-VTSB)") (class "Default")
      (node (ref "R_TH") (pin "2") (pinfunction "2_2") (pintype "passive"))
      (node (ref "U$6") (pin "15") (pinfunction "VTSB_15") (pintype "bidirectional"))
    )
    (net (code "65") (name "Net-(U$6-ZEDE)") (class "Default")
      (node (ref "R_PGM1") (pin "2") (pinfunction "2_2") (pintype "passive"))
      (node (ref "U$6") (pin "22") (pinfunction "ZEDE_22") (pintype "bidirectional"))
      (node (ref "U$9") (pin "P3") (pinfunction "P3_P3") (pintype "bidirectional"))
    )
    (net (code "66") (name "unconnected-(U$2-TAB-PadP$6)") (class "Default")
      (node (ref "U$2") (pin "P$6") (pinfunction "TAB_P$6") (pintype "bidirectional"))
    )
    (net (code "67") (name "unconnected-(U$2-TAB-PadP$7)") (class "Default")
      (node (ref "U$2") (pin "P$7") (pinfunction "TAB_P$7") (pintype "bidirectional"))
    )
    (net (code "68") (name "unconnected-(U$9-P$1-PadP$6)") (class "Default")
      (node (ref "U$9") (pin "P$6") (pinfunction "P$1_P$6") (pintype "bidirectional"))
    )
    (net (code "69") (name "unconnected-(U$9-P$2-PadP$7)") (class "Default")
      (node (ref "U$9") (pin "P$7") (pinfunction "P$2_P$7") (pintype "bidirectional"))
    )
  )
)
